# potentiometer_breakout.net
KiCad netlist of a schematic drawn in EAGLE
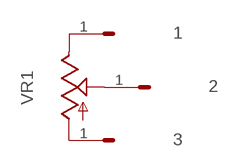
[diagram p0: schematic, sheet 1]

(export (version "E")
  (design (tool "Eeschema 10.0.6"))
  (components
    (comp (ref "1")
      (value "HEADER/MALE/01")
      (footprint "eagle-import:HEADER_MALE_01")
      (libsource (lib "eagle-import") (part "HEADER/MALE/01"))
    )
    (comp (ref "2")
      (value "HEADER/MALE/01")
      (footprint "eagle-import:HEADER_MALE_01")
      (libsource (lib "eagle-import") (part "HEADER/MALE/01"))
    )
    (comp (ref "3")
      (value "HEADER/MALE/01")
      (footprint "eagle-import:HEADER_MALE_01")
      (libsource (lib "eagle-import") (part "HEADER/MALE/01"))
    )
    (comp (ref "VR1")
      (value "9MM_SNAP-IN_POT_")
      (footprint "eagle-import:9MM_SNAP-IN_POT")
      (libsource (lib "eagle-import") (part "9MM_SNAP-IN_POT_"))
    )
  )
  (nets
    (net (code "1") (name "Net-(1-3)") (class "Default")
      (node (ref "1") (pin "1") (pinfunction "3_1") (pintype "passive"))
      (node (ref "VR1") (pin "3") (pinfunction "E_3") (pintype "passive"))
    )
    (net (code "2") (name "Net-(2-3)") (class "Default")
      (node (ref "2") (pin "1") (pinfunction "3_1") (pintype "passive"))
      (node (ref "VR1") (pin "2") (pinfunction "S_2") (pintype "passive"))
    )
    (net (code "3") (name "Net-(3-3)") (class "Default")
      (node (ref "3") (pin "1") (pinfunction "3_1") (pintype "passive"))
      (node (ref "VR1") (pin "1") (pinfunction "A_1") (pintype "passive"))
    )
  )
)
